# Data_Blue.net
KiCad netlist of a schematic drawn in Altium Designer
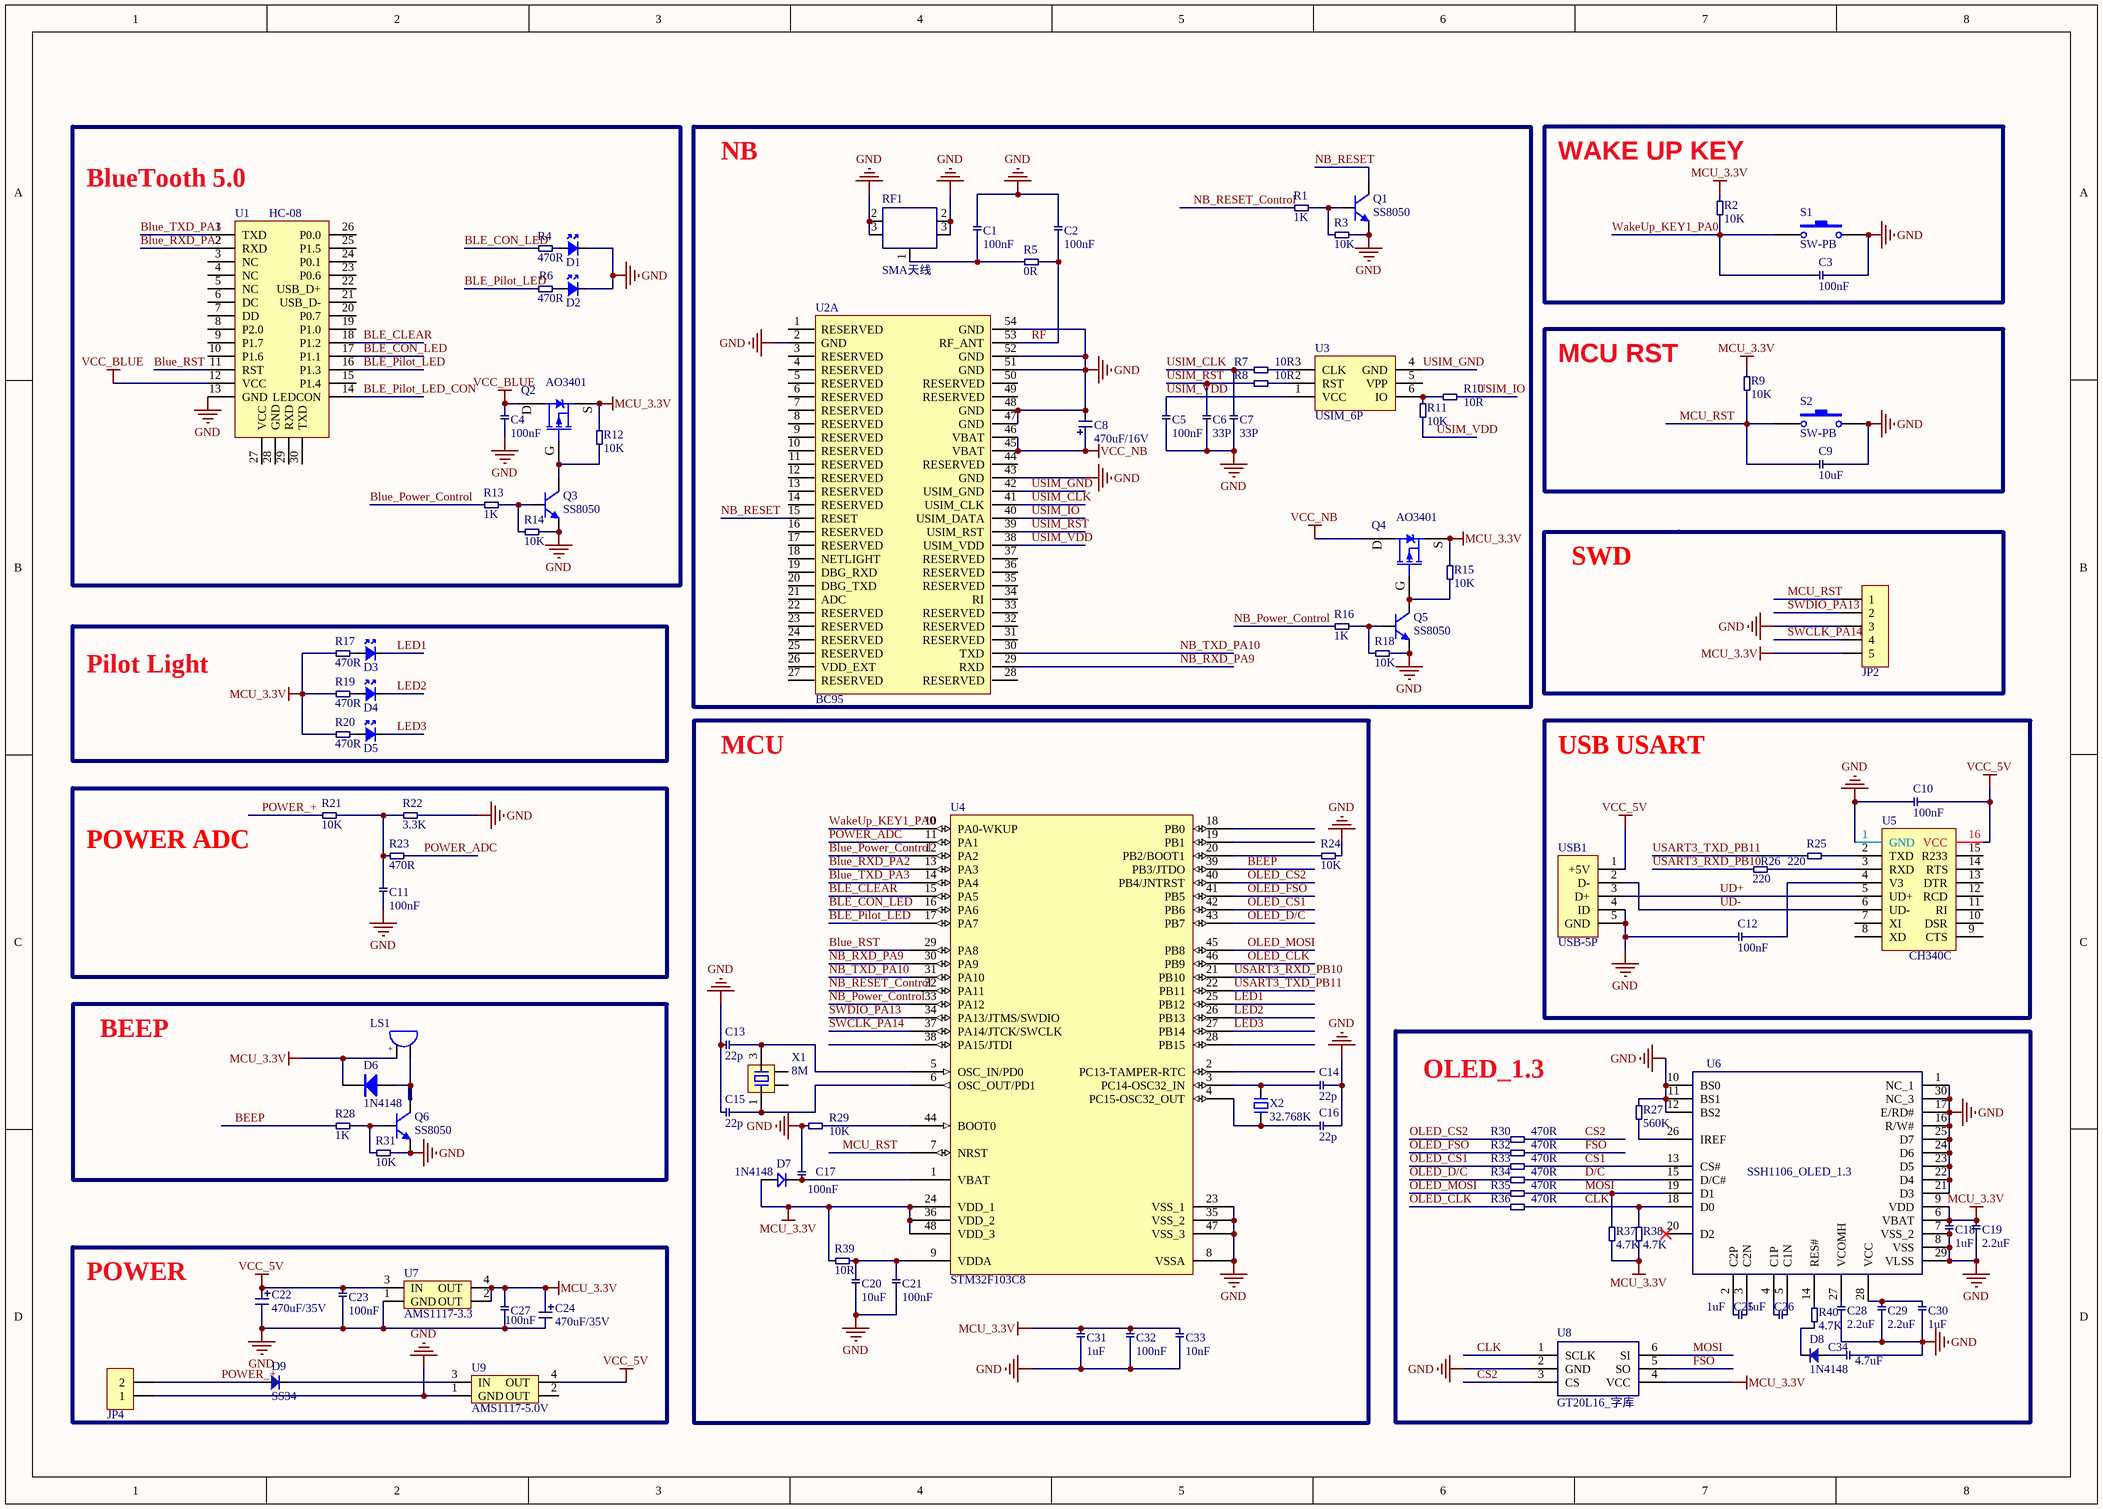
[diagram p0: Data_Blue.SchDoc]

(export (version "E")
  (design (tool "Eeschema 10.0.6"))
  (components
    (comp (ref "C1") (value "100nF") (footprint "0603CC") (libsource (lib "LFZ@WLP") (part "cap")))
    (comp (ref "C2") (value "100nF") (footprint "0603CC") (libsource (lib "LFZ@WLP") (part "cap")))
    (comp (ref "C3") (value "100nF") (footprint "0603CC") (libsource (lib "LFZ@WLP") (part "cap")))
    (comp (ref "C4") (value "100nF") (footprint "0603CC") (libsource (lib "LFZ@WLP") (part "cap")))
    (comp (ref "C5") (value "100nF") (footprint "0603CC") (libsource (lib "LFZ@WLP") (part "cap")))
    (comp (ref "C6") (value "33P") (footprint "0603CC") (libsource (lib "LFZ@WLP") (part "cap")))
    (comp (ref "C7") (value "33P") (footprint "0603CC") (libsource (lib "LFZ@WLP") (part "cap")))
    (comp (ref "C8") (value "470uF/16V") (footprint "C3216") (libsource (lib "LFZ@WLP") (part "Ecap")))
    (comp (ref "C9") (value "10uF") (footprint "0603CC") (libsource (lib "LFZ@WLP") (part "cap")))
    (comp (ref "C10") (value "100nF") (footprint "0603CC") (libsource (lib "LFZ@WLP") (part "cap")))
    (comp (ref "C11") (value "100nF") (footprint "0603CC") (libsource (lib "LFZ@WLP") (part "cap")))
    (comp (ref "C12") (value "100nF") (footprint "0603CC") (libsource (lib "LFZ@WLP") (part "cap")))
    (comp (ref "C13") (value "22p") (footprint "0603CC") (libsource (lib "LFZ@WLP") (part "cap")))
    (comp (ref "C14") (value "22p") (footprint "0603CC") (libsource (lib "LFZ@WLP") (part "cap")))
    (comp (ref "C15") (value "22p") (footprint "0603CC") (libsource (lib "LFZ@WLP") (part "cap")))
    (comp (ref "C16") (value "22p") (footprint "0603CC") (libsource (lib "LFZ@WLP") (part "cap")))
    (comp (ref "C17") (value "100nF") (footprint "0603CC") (libsource (lib "LFZ@WLP") (part "cap")))
    (comp (ref "C18") (value "1uF") (footprint "0603CC") (libsource (lib "LFZ@WLP") (part "cap")))
    (comp (ref "C19") (value "2.2uF") (footprint "0603CC") (libsource (lib "LFZ@WLP") (part "cap")))
    (comp (ref "C20") (value "10uF") (footprint "0603CC") (libsource (lib "LFZ@WLP") (part "cap")))
    (comp (ref "C21") (value "100nF") (footprint "0603CC") (libsource (lib "LFZ@WLP") (part "cap")))
    (comp (ref "C22") (value "470uF/35V") (footprint "CD A(3216)") (libsource (lib "LFZ@WLP") (part "Ecap")))
    (comp (ref "C23") (value "100nF") (footprint "0603CC") (libsource (lib "LFZ@WLP") (part "cap")))
    (comp (ref "C24") (value "470uF/35V") (footprint "C3216") (libsource (lib "LFZ@WLP") (part "Ecap")))
    (comp (ref "C25") (value "1uF") (footprint "0603CC") (libsource (lib "LFZ@WLP") (part "cap")))
    (comp (ref "C26") (value "1uF") (footprint "0603CC") (libsource (lib "LFZ@WLP") (part "cap")))
    (comp (ref "C27") (value "100nF") (footprint "0603CC") (libsource (lib "LFZ@WLP") (part "cap")))
    (comp (ref "C28") (value "2.2uF") (footprint "0603CC") (libsource (lib "LFZ@WLP") (part "cap")))
    (comp (ref "C29") (value "2.2uF") (footprint "0603CC") (libsource (lib "LFZ@WLP") (part "cap")))
    (comp (ref "C30") (value "1uF") (footprint "0603CC") (libsource (lib "LFZ@WLP") (part "cap")))
    (comp (ref "C31") (value "1uF") (footprint "0603CC") (libsource (lib "LFZ@WLP") (part "cap")))
    (comp (ref "C32") (value "100nF") (footprint "0603CC") (libsource (lib "LFZ@WLP") (part "cap")))
    (comp (ref "C33") (value "10nF") (footprint "0603CC") (libsource (lib "LFZ@WLP") (part "cap")))
    (comp (ref "C34") (value "4.7uF") (footprint "0603CC") (libsource (lib "LFZ@WLP") (part "cap")))
    (comp (ref "D1") (value "LED") (footprint "LED 0603G") (libsource (lib "LFZ@WLP") (part "LED")))
    (comp (ref "D2") (value "LED") (footprint "LED 0603R") (libsource (lib "LFZ@WLP") (part "LED")))
    (comp (ref "D3") (value "LED") (footprint "LED 3MM-G") (libsource (lib "LFZ@WLP") (part "LED")))
    (comp (ref "D4") (value "LED") (footprint "LED 3MM-G") (libsource (lib "LFZ@WLP") (part "LED")))
    (comp (ref "D5") (value "LED") (footprint "LED 3MM-G") (libsource (lib "LFZ@WLP") (part "LED")))
    (comp (ref "D6")
      (value "1N4148")
      (footprint "SOD-323")
      (description "高速开关二极管")
      (libsource (lib "8.1   - 二极管-整流桥") (part "1N4148"))
    )
    (comp (ref "D7")
      (value "1N4148")
      (footprint "SOD-323")
      (libsource (lib "WarShip V3 STM32103封装库") (part "D"))
    )
    (comp (ref "D8") (value "1N4148") (footprint "SOD-523") (libsource (lib "LFZ@WLP") (part "Diod")))
    (comp (ref "D9") (value "SS34") (footprint "SMA") (libsource (lib "Diod") (part "Diod")))
    (comp (ref "JP2")
      (value "HDR-1X5")
      (footprint "HDR2.54-LI-5P")
      (description "5P接插件")
      (libsource (lib "4.5   - 接插件-脚距2.54") (part "Header 5"))
    )
    (comp (ref "JP4")
      (value "HDR-1X2")
      (footprint "XH2.54-WI-2P")
      (description "2P接插件")
      (libsource (lib "4.5   - 接插件-脚距2.54") (part "Header 2"))
    )
    (comp (ref "LS1")
      (value "DC5V")
      (footprint "BEEP 5x9x5.5")
      (description "蜂鸣器")
      (libsource (lib "15.1 - 未分类器件") (part "BEEP"))
    )
    (comp (ref "Q1")
      (value "SS8050")
      (footprint "SOT23-3N")
      (description "高频放大-NPN型")
      (libsource (lib "6.2   - 三极管") (part "8050-SMD"))
    )
    (comp (ref "Q2")
      (value "AO3401")
      (footprint "SOT23-3N")
      (description "P沟道场效应管")
      (libsource (lib "6.1   - 场效应管-可控硅") (part "SI2301"))
    )
    (comp (ref "Q3")
      (value "SS8050")
      (footprint "SOT23-3N")
      (description "高频放大-NPN型")
      (libsource (lib "6.2   - 三极管") (part "8050-SMD"))
    )
    (comp (ref "Q4")
      (value "AO3401")
      (footprint "SOT23-3N")
      (description "P沟道场效应管")
      (libsource (lib "6.1   - 场效应管-可控硅") (part "SI2301"))
    )
    (comp (ref "Q5")
      (value "SS8050")
      (footprint "SOT23-3N")
      (description "高频放大-NPN型")
      (libsource (lib "6.2   - 三极管") (part "8050-SMD"))
    )
    (comp (ref "Q6")
      (value "SS8050")
      (footprint "SOT23-3N")
      (description "高频放大-NPN型")
      (libsource (lib "6.2   - 三极管") (part "8050-SMD"))
    )
    (comp (ref "R1") (value "1K") (footprint "0603RR") (libsource (lib "LFZ@WLP") (part "res")))
    (comp (ref "R2") (value "10K") (footprint "0603RR") (libsource (lib "LFZ@WLP") (part "res")))
    (comp (ref "R3") (value "10K") (footprint "0603RR") (libsource (lib "LFZ@WLP") (part "res")))
    (comp (ref "R4") (value "470R") (footprint "0603RR") (libsource (lib "LFZ@WLP") (part "res")))
    (comp (ref "R5") (value "0R") (footprint "0603RR") (libsource (lib "LFZ@WLP") (part "res")))
    (comp (ref "R6") (value "470R") (footprint "0603RR") (libsource (lib "LFZ@WLP") (part "res")))
    (comp (ref "R7") (value "10R") (footprint "0603RR") (libsource (lib "LFZ@WLP") (part "res")))
    (comp (ref "R8") (value "10R") (footprint "0603RR") (libsource (lib "LFZ@WLP") (part "res")))
    (comp (ref "R9") (value "10K") (footprint "0603RR") (libsource (lib "LFZ@WLP") (part "res")))
    (comp (ref "R10") (value "10R") (footprint "0603RR") (libsource (lib "LFZ@WLP") (part "res")))
    (comp (ref "R11") (value "10K") (footprint "0603RR") (libsource (lib "LFZ@WLP") (part "res")))
    (comp (ref "R12") (value "10K") (footprint "0603RR") (libsource (lib "LFZ@WLP") (part "res")))
    (comp (ref "R13") (value "1K") (footprint "0603RR") (libsource (lib "LFZ@WLP") (part "res")))
    (comp (ref "R14") (value "10K") (footprint "0603RR") (libsource (lib "LFZ@WLP") (part "res")))
    (comp (ref "R15") (value "10K") (footprint "0603RR") (libsource (lib "LFZ@WLP") (part "res")))
    (comp (ref "R16") (value "1K") (footprint "0603RR") (libsource (lib "LFZ@WLP") (part "res")))
    (comp (ref "R17") (value "470R") (footprint "0603RR") (libsource (lib "LFZ@WLP") (part "res")))
    (comp (ref "R18") (value "10K") (footprint "0603RR") (libsource (lib "LFZ@WLP") (part "res")))
    (comp (ref "R19") (value "470R") (footprint "0603RR") (libsource (lib "LFZ@WLP") (part "res")))
    (comp (ref "R20") (value "470R") (footprint "0603RR") (libsource (lib "LFZ@WLP") (part "res")))
    (comp (ref "R21") (value "10K") (footprint "0603RR") (libsource (lib "LFZ@WLP") (part "res")))
    (comp (ref "R22") (value "3.3K") (footprint "0603RR") (libsource (lib "LFZ@WLP") (part "res")))
    (comp (ref "R23") (value "470R") (footprint "0603RR") (libsource (lib "LFZ@WLP") (part "res")))
    (comp (ref "R24") (value "10K") (footprint "0603RR") (libsource (lib "LFZ@WLP") (part "res")))
    (comp (ref "R25") (value "220") (footprint "0603RR") (libsource (lib "LFZ@WLP") (part "res")))
    (comp (ref "R26") (value "220") (footprint "0603RR") (libsource (lib "LFZ@WLP") (part "res")))
    (comp (ref "R27") (value "560K") (footprint "0603RR") (libsource (lib "LFZ@WLP") (part "res")))
    (comp (ref "R28") (value "1K") (footprint "0603RR") (libsource (lib "LFZ@WLP") (part "res")))
    (comp (ref "R29") (value "10K") (footprint "0603RR") (libsource (lib "LFZ@WLP") (part "res")))
    (comp (ref "R30") (value "470R") (footprint "0603RR") (libsource (lib "LFZ@WLP") (part "res")))
    (comp (ref "R31") (value "10K") (footprint "0603RR") (libsource (lib "LFZ@WLP") (part "res")))
    (comp (ref "R32") (value "470R") (footprint "0603RR") (libsource (lib "LFZ@WLP") (part "res")))
    (comp (ref "R33") (value "470R") (footprint "0603RR") (libsource (lib "LFZ@WLP") (part "res")))
    (comp (ref "R34") (value "470R") (footprint "0603RR") (libsource (lib "LFZ@WLP") (part "res")))
    (comp (ref "R35") (value "470R") (footprint "0603RR") (libsource (lib "LFZ@WLP") (part "res")))
    (comp (ref "R36") (value "470R") (footprint "0603RR") (libsource (lib "LFZ@WLP") (part "res")))
    (comp (ref "R37") (value "4.7K") (footprint "0603RR") (libsource (lib "LFZ@WLP") (part "res")))
    (comp (ref "R38") (value "4.7K") (footprint "0603RR") (libsource (lib "LFZ@WLP") (part "res")))
    (comp (ref "R39") (value "10R") (footprint "0603RR") (libsource (lib "LFZ@WLP") (part "res")))
    (comp (ref "R40") (value "4.7K") (footprint "0603RR") (libsource (lib "LFZ@WLP") (part "res")))
    (comp (ref "RF1") (value "SMA天线") (footprint "SMA_FR") (libsource (lib "LFZ@WLP") (part "SMA天线")))
    (comp (ref "S1")
      (value "SW-PB")
      (footprint "TSW SMD-6*6*6")
      (description "Switch")
      (libsource (lib "开关及电源") (part "SW-PB"))
    )
    (comp (ref "S2")
      (value "SW-PB")
      (footprint "TSW SMD-4*4*1.5")
      (description "Switch")
      (libsource (lib "开关及电源") (part "SW-PB"))
    )
    (comp (ref "U1") (value "HC-08") (footprint "HC-08") (libsource (lib "LFZ@WLP") (part "HC-08")))
    (comp (ref "U2")
      (value "BC95")
      (footprint "BC95")
      (libsource (lib "Quectel_BC95_SCH_Part_Protel&AD_20170925") (part "BC95"))
    )
    (comp (ref "U3") (value "USIM_6P") (footprint "SIM 6P 自弹") (libsource (lib "XG-BM02") (part "USIM-6P")))
    (comp (ref "U4")
      (value "STM32F103C8")
      (footprint "LQFP48 7X7_M")
      (description "Flaah:64/RAM:20/IO:36")
      (libsource (lib "2.1   - STM32系列单片机") (part "STM32F103C8"))
    )
    (comp (ref "U5") (value "CH340C") (footprint "SOP16_L") (libsource (lib "LFZ@WLP") (part "CH340C")))
    (comp (ref "U6")
      (value "SSH1106_OLED_1.3")
      (footprint "OLED_1.3_FPC_30")
      (libsource (lib "LFZ@WLP") (part "SSH1106_OLED_1.3"))
    )
    (comp (ref "U7")
      (value "AMS1117-3.3")
      (footprint "SOT223_N")
      (libsource (lib "WarShip V3 STM32103封装库") (part "AMS1117"))
    )
    (comp (ref "U8")
      (value "GT20L16_字库")
      (footprint "SOT23-6")
      (libsource (lib "LFZ@WLP") (part "GT20L16_字库"))
    )
    (comp (ref "U9")
      (value "AMS1117-5.0V")
      (footprint "SOT223_N")
      (libsource (lib "WarShip V3 STM32103封装库") (part "AMS1117"))
    )
    (comp (ref "USB1")
      (value "USB-5P")
      (footprint "USB-MICRO_A")
      (description "微型USB母座")
      (libsource (lib "4.1   - 接口类") (part "USB-5P"))
    )
    (comp (ref "X1")
      (value "8M")
      (footprint "OSC 3225-4P")
      (description "4脚无源晶振")
      (libsource (lib "10.1 - 保险丝-晶振") (part "XTAL-4P"))
    )
    (comp (ref "X2")
      (value "32.768K")
      (footprint "OSC 3215-2P")
      (description "2脚无源脚晶振")
      (libsource (lib "10.1 - 保险丝-晶振") (part "XTAL-2P"))
    )
  )
  (nets
    (net (code "1") (name "/BEEP") (class "Default")
      (node (ref "R28") (pin "1") (pinfunction "1_1") (pintype "passive"))
      (node (ref "U4") (pin "39") (pinfunction "PB3/JTDO_39") (pintype "bidirectional"))
    )
    (net (code "2") (name "/BLE_CLEAR") (class "Default")
      (node (ref "U1") (pin "18") (pinfunction "P1.2_18") (pintype "passive"))
      (node (ref "U4") (pin "15") (pinfunction "PA5_15") (pintype "bidirectional"))
    )
    (net (code "3") (name "/BLE_CON_LED") (class "Default")
      (node (ref "R4") (pin "1") (pinfunction "1_1") (pintype "passive"))
      (node (ref "U1") (pin "17") (pinfunction "P1.1_17") (pintype "passive"))
      (node (ref "U4") (pin "16") (pinfunction "PA6_16") (pintype "bidirectional"))
    )
    (net (code "4") (name "/BLE_Pilot_LED") (class "Default")
      (node (ref "R6") (pin "1") (pinfunction "1_1") (pintype "passive"))
      (node (ref "U1") (pin "16") (pinfunction "P1.3_16") (pintype "passive"))
      (node (ref "U4") (pin "17") (pinfunction "PA7_17") (pintype "bidirectional"))
    )
    (net (code "5") (name "/BLE_Pilot_LED_CON") (class "Default")
      (node (ref "U1") (pin "14") (pinfunction "LEDCON_14") (pintype "passive"))
    )
    (net (code "6") (name "/Blue_Power_Control") (class "Default")
      (node (ref "R13") (pin "1") (pinfunction "1_1") (pintype "passive"))
      (node (ref "U4") (pin "12") (pinfunction "PA2_12") (pintype "bidirectional"))
    )
    (net (code "7") (name "/Blue_RST") (class "Default")
      (node (ref "U1") (pin "11") (pinfunction "RST_11") (pintype "passive"))
      (node (ref "U4") (pin "29") (pinfunction "PA8_29") (pintype "bidirectional"))
    )
    (net (code "8") (name "/Blue_RXD_PA2") (class "Default")
      (node (ref "U1") (pin "2") (pinfunction "RXD_2") (pintype "passive"))
      (node (ref "U4") (pin "13") (pinfunction "PA3_13") (pintype "bidirectional"))
    )
    (net (code "9") (name "/Blue_TXD_PA3") (class "Default")
      (node (ref "U1") (pin "1") (pinfunction "TXD_1") (pintype "passive"))
      (node (ref "U4") (pin "14") (pinfunction "PA4_14") (pintype "bidirectional"))
    )
    (net (code "10") (name "/CLK") (class "Default")
      (node (ref "R36") (pin "2") (pinfunction "2_2") (pintype "passive"))
      (node (ref "R38") (pin "2") (pinfunction "2_2") (pintype "passive"))
      (node (ref "U6") (pin "18") (pinfunction "D0_18") (pintype "passive"))
      (node (ref "U8") (pin "1") (pinfunction "SCLK_1") (pintype "passive"))
    )
    (net (code "11") (name "/CS1") (class "Default")
      (node (ref "R33") (pin "2") (pinfunction "2_2") (pintype "passive"))
      (node (ref "U6") (pin "13") (pinfunction "CS#_13") (pintype "passive"))
    )
    (net (code "12") (name "/CS2") (class "Default")
      (node (ref "R30") (pin "2") (pinfunction "2_2") (pintype "passive"))
      (node (ref "U8") (pin "3") (pinfunction "CS_3") (pintype "passive"))
    )
    (net (code "13") (name "/D{slash}C") (class "Default")
      (node (ref "R34") (pin "2") (pinfunction "2_2") (pintype "passive"))
      (node (ref "U6") (pin "15") (pinfunction "D/C#_15") (pintype "passive"))
    )
    (net (code "14") (name "/FSO") (class "Default")
      (node (ref "R32") (pin "2") (pinfunction "2_2") (pintype "passive"))
      (node (ref "U8") (pin "5") (pinfunction "SO_5") (pintype "passive"))
    )
    (net (code "15") (name "/LED1") (class "Default")
      (node (ref "D3") (pin "2") (pinfunction "CATHODE_2") (pintype "passive"))
      (node (ref "U4") (pin "25") (pinfunction "PB12_25") (pintype "bidirectional"))
    )
    (net (code "16") (name "/LED2") (class "Default")
      (node (ref "D4") (pin "2") (pinfunction "CATHODE_2") (pintype "passive"))
      (node (ref "U4") (pin "26") (pinfunction "PB13_26") (pintype "bidirectional"))
    )
    (net (code "17") (name "/LED3") (class "Default")
      (node (ref "D5") (pin "2") (pinfunction "CATHODE_2") (pintype "passive"))
      (node (ref "U4") (pin "27") (pinfunction "PB14_27") (pintype "bidirectional"))
    )
    (net (code "18") (name "/MCU_RST") (class "Default")
      (node (ref "C9") (pin "2") (pinfunction "2_2") (pintype "passive"))
      (node (ref "JP2") (pin "1") (pinfunction "1_1") (pintype "passive"))
      (node (ref "R9") (pin "1") (pinfunction "1_1") (pintype "passive"))
      (node (ref "S2") (pin "1") (pinfunction "1_1") (pintype "passive"))
      (node (ref "U4") (pin "7") (pinfunction "NRST_7") (pintype "bidirectional"))
    )
    (net (code "19") (name "/MOSI") (class "Default")
      (node (ref "R35") (pin "2") (pinfunction "2_2") (pintype "passive"))
      (node (ref "R37") (pin "2") (pinfunction "2_2") (pintype "passive"))
      (node (ref "U6") (pin "19") (pinfunction "D1_19") (pintype "passive"))
      (node (ref "U8") (pin "6") (pinfunction "SI_6") (pintype "passive"))
    )
    (net (code "20") (name "/NB_Power_Control") (class "Default")
      (node (ref "R16") (pin "1") (pinfunction "1_1") (pintype "passive"))
      (node (ref "U4") (pin "33") (pinfunction "PA12_33") (pintype "bidirectional"))
    )
    (net (code "21") (name "/NB_RESET") (class "Default")
      (node (ref "Q1") (pin "3") (pinfunction "C_3") (pintype "passive"))
      (node (ref "U2") (pin "15") (pinfunction "RESET_15") (pintype "passive"))
    )
    (net (code "22") (name "/NB_RESET_Control") (class "Default")
      (node (ref "R1") (pin "1") (pinfunction "1_1") (pintype "passive"))
      (node (ref "U4") (pin "32") (pinfunction "PA11_32") (pintype "bidirectional"))
    )
    (net (code "23") (name "/NB_RXD_PA9") (class "Default")
      (node (ref "U2") (pin "29") (pinfunction "RXD_29") (pintype "passive"))
      (node (ref "U4") (pin "30") (pinfunction "PA9_30") (pintype "bidirectional"))
    )
    (net (code "24") (name "/NB_TXD_PA10") (class "Default")
      (node (ref "U2") (pin "30") (pinfunction "TXD_30") (pintype "passive"))
      (node (ref "U4") (pin "31") (pinfunction "PA10_31") (pintype "bidirectional"))
    )
    (net (code "25") (name "/OLED_CLK") (class "Default")
      (node (ref "R36") (pin "1") (pinfunction "1_1") (pintype "passive"))
      (node (ref "U4") (pin "46") (pinfunction "PB9_46") (pintype "bidirectional"))
    )
    (net (code "26") (name "/OLED_CS1") (class "Default")
      (node (ref "R33") (pin "1") (pinfunction "1_1") (pintype "passive"))
      (node (ref "U4") (pin "42") (pinfunction "PB6_42") (pintype "bidirectional"))
    )
    (net (code "27") (name "/OLED_CS2") (class "Default")
      (node (ref "R30") (pin "1") (pinfunction "1_1") (pintype "passive"))
      (node (ref "U4") (pin "40") (pinfunction "PB4/JNTRST_40") (pintype "bidirectional"))
    )
    (net (code "28") (name "/OLED_D{slash}C") (class "Default")
      (node (ref "R34") (pin "1") (pinfunction "1_1") (pintype "passive"))
      (node (ref "U4") (pin "43") (pinfunction "PB7_43") (pintype "bidirectional"))
    )
    (net (code "29") (name "/OLED_FSO") (class "Default")
      (node (ref "R32") (pin "1") (pinfunction "1_1") (pintype "passive"))
      (node (ref "U4") (pin "41") (pinfunction "PB5_41") (pintype "bidirectional"))
    )
    (net (code "30") (name "/OLED_MOSI") (class "Default")
      (node (ref "R35") (pin "1") (pinfunction "1_1") (pintype "passive"))
      (node (ref "U4") (pin "45") (pinfunction "PB8_45") (pintype "bidirectional"))
    )
    (net (code "31") (name "/POWER_+") (class "Default")
      (node (ref "D9") (pin "1") (pinfunction "ANODE_1") (pintype "passive"))
      (node (ref "JP4") (pin "2") (pinfunction "2_2") (pintype "passive"))
      (node (ref "R21") (pin "1") (pinfunction "1_1") (pintype "passive"))
    )
    (net (code "32") (name "/POWER_ADC") (class "Default")
      (node (ref "R23") (pin "1") (pinfunction "1_1") (pintype "passive"))
      (node (ref "U4") (pin "11") (pinfunction "PA1_11") (pintype "bidirectional"))
    )
    (net (code "33") (name "/RF") (class "Default")
      (node (ref "C2") (pin "1") (pinfunction "1_1") (pintype "passive"))
      (node (ref "R5") (pin "1") (pinfunction "1_1") (pintype "passive"))
      (node (ref "U2") (pin "53") (pinfunction "RF_ANT_53") (pintype "passive"))
    )
    (net (code "34") (name "/SWCLK_PA14") (class "Default")
      (node (ref "JP2") (pin "4") (pinfunction "4_4") (pintype "passive"))
      (node (ref "U4") (pin "37") (pinfunction "PA14/JTCK/SWCLK_37") (pintype "bidirectional"))
    )
    (net (code "35") (name "/SWDIO_PA13") (class "Default")
      (node (ref "JP2") (pin "2") (pinfunction "2_2") (pintype "passive"))
      (node (ref "U4") (pin "34") (pinfunction "PA13/JTMS/SWDIO_34") (pintype "bidirectional"))
    )
    (net (code "36") (name "/UD+") (class "Default")
      (node (ref "U5") (pin "5") (pinfunction "UD+_5") (pintype "passive"))
      (node (ref "USB1") (pin "3") (pinfunction "D+_3") (pintype "passive"))
    )
    (net (code "37") (name "/UD-") (class "Default")
      (node (ref "U5") (pin "6") (pinfunction "UD-_6") (pintype "passive"))
      (node (ref "USB1") (pin "2") (pinfunction "D-_2") (pintype "passive"))
    )
    (net (code "38") (name "/USART3_RXD_PB10") (class "Default")
      (node (ref "R26") (pin "1") (pinfunction "1_1") (pintype "passive"))
      (node (ref "U4") (pin "21") (pinfunction "PB10_21") (pintype "bidirectional"))
    )
    (net (code "39") (name "/USART3_TXD_PB11") (class "Default")
      (node (ref "R25") (pin "1") (pinfunction "1_1") (pintype "passive"))
      (node (ref "U4") (pin "22") (pinfunction "PB11_22") (pintype "bidirectional"))
    )
    (net (code "40") (name "/USIM_CLK") (class "Default")
      (node (ref "C7") (pin "2") (pinfunction "2_2") (pintype "passive"))
      (node (ref "R7") (pin "1") (pinfunction "1_1") (pintype "passive"))
      (node (ref "U2") (pin "41") (pinfunction "USIM_CLK_41") (pintype "passive"))
    )
    (net (code "41") (name "/USIM_GND") (class "Default")
      (node (ref "U2") (pin "42") (pinfunction "USIM_GND_42") (pintype "passive"))
      (node (ref "U3") (pin "4") (pinfunction "GND_4") (pintype "passive"))
    )
    (net (code "42") (name "/USIM_IO") (class "Default")
      (node (ref "R10") (pin "1") (pinfunction "1_1") (pintype "passive"))
      (node (ref "U2") (pin "40") (pinfunction "USIM_DATA_40") (pintype "passive"))
    )
    (net (code "43") (name "/USIM_RST") (class "Default")
      (node (ref "C6") (pin "2") (pinfunction "2_2") (pintype "passive"))
      (node (ref "R8") (pin "1") (pinfunction "1_1") (pintype "passive"))
      (node (ref "U2") (pin "39") (pinfunction "USIM_RST_39") (pintype "passive"))
    )
    (net (code "44") (name "/USIM_VDD") (class "Default")
      (node (ref "C5") (pin "2") (pinfunction "2_2") (pintype "passive"))
      (node (ref "R11") (pin "1") (pinfunction "1_1") (pintype "passive"))
      (node (ref "U2") (pin "38") (pinfunction "USIM_VDD_38") (pintype "passive"))
      (node (ref "U3") (pin "1") (pinfunction "VCC_1") (pintype "passive"))
    )
    (net (code "45") (name "/WakeUp_KEY1_PA0") (class "Default")
      (node (ref "C3") (pin "1") (pinfunction "1_1") (pintype "passive"))
      (node (ref "R2") (pin "1") (pinfunction "1_1") (pintype "passive"))
      (node (ref "S1") (pin "1") (pinfunction "1_1") (pintype "passive"))
      (node (ref "U4") (pin "10") (pinfunction "PA0-WKUP_10") (pintype "bidirectional"))
    )
    (net (code "46") (name "GND") (class "Default")
      (node (ref "C1") (pin "2") (pinfunction "2_2") (pintype "passive"))
      (node (ref "C10") (pin "2") (pinfunction "2_2") (pintype "passive"))
      (node (ref "C11") (pin "1") (pinfunction "1_1") (pintype "passive"))
      (node (ref "C12") (pin "2") (pinfunction "2_2") (pintype "passive"))
      (node (ref "C13") (pin "1") (pinfunction "1_1") (pintype "passive"))
      (node (ref "C14") (pin "2") (pinfunction "2_2") (pintype "passive"))
      (node (ref "C15") (pin "1") (pinfunction "1_1") (pintype "passive"))
      (node (ref "C16") (pin "2") (pinfunction "2_2") (pintype "passive"))
      (node (ref "C17") (pin "2") (pinfunction "2_2") (pintype "passive"))
      (node (ref "C18") (pin "1") (pinfunction "1_1") (pintype "passive"))
      (node (ref "C19") (pin "1") (pinfunction "1_1") (pintype "passive"))
      (node (ref "C2") (pin "2") (pinfunction "2_2") (pintype "passive"))
      (node (ref "C20") (pin "1") (pinfunction "1_1") (pintype "passive"))
      (node (ref "C21") (pin "1") (pinfunction "1_1") (pintype "passive"))
      (node (ref "C22") (pin "2") (pinfunction "2_2") (pintype "passive"))
      (node (ref "C23") (pin "1") (pinfunction "1_1") (pintype "passive"))
      (node (ref "C24") (pin "2") (pinfunction "2_2") (pintype "passive"))
      (node (ref "C27") (pin "1") (pinfunction "1_1") (pintype "passive"))
      (node (ref "C28") (pin "1") (pinfunction "1_1") (pintype "passive"))
      (node (ref "C29") (pin "1") (pinfunction "1_1") (pintype "passive"))
      (node (ref "C3") (pin "2") (pinfunction "2_2") (pintype "passive"))
      (node (ref "C30") (pin "1") (pinfunction "1_1") (pintype "passive"))
      (node (ref "C31") (pin "1") (pinfunction "1_1") (pintype "passive"))
      (node (ref "C32") (pin "1") (pinfunction "1_1") (pintype "passive"))
      (node (ref "C33") (pin "1") (pinfunction "1_1") (pintype "passive"))
      (node (ref "C34") (pin "1") (pinfunction "1_1") (pintype "passive"))
      (node (ref "C4") (pin "1") (pinfunction "1_1") (pintype "passive"))
      (node (ref "C5") (pin "1") (pinfunction "1_1") (pintype "passive"))
      (node (ref "C6") (pin "1") (pinfunction "1_1") (pintype "passive"))
      (node (ref "C7") (pin "1") (pinfunction "1_1") (pintype "passive"))
      (node (ref "C8") (pin "2") (pinfunction "2_2") (pintype "passive"))
      (node (ref "C9") (pin "1") (pinfunction "1_1") (pintype "passive"))
      (node (ref "D1") (pin "2") (pinfunction "CATHODE_2") (pintype "passive"))
      (node (ref "D2") (pin "2") (pinfunction "CATHODE_2") (pintype "passive"))
      (node (ref "JP2") (pin "3") (pinfunction "3_3") (pintype "passive"))
      (node (ref "JP4") (pin "1") (pinfunction "1_1") (pintype "passive"))
      (node (ref "Q1") (pin "2") (pinfunction "E_2") (pintype "passive"))
      (node (ref "Q3") (pin "2") (pinfunction "E_2") (pintype "passive"))
      (node (ref "Q5") (pin "2") (pinfunction "E_2") (pintype "passive"))
      (node (ref "Q6") (pin "2") (pinfunction "E_2") (pintype "passive"))
      (node (ref "R14") (pin "2") (pinfunction "2_2") (pintype "passive"))
      (node (ref "R18") (pin "2") (pinfunction "2_2") (pintype "passive"))
      (node (ref "R22") (pin "2") (pinfunction "2_2") (pintype "passive"))
      (node (ref "R24") (pin "2") (pinfunction "2_2") (pintype "passive"))
      (node (ref "R27") (pin "2") (pinfunction "2_2") (pintype "passive"))
      (node (ref "R29") (pin "1") (pinfunction "1_1") (pintype "passive"))
      (node (ref "R3") (pin "2") (pinfunction "2_2") (pintype "passive"))
      (node (ref "R31") (pin "2") (pinfunction "2_2") (pintype "passive"))
      (node (ref "RF1") (pin "2") (pinfunction "5_2") (pintype "passive"))
      (node (ref "RF1") (pin "3") (pinfunction "3_3") (pintype "passive"))
      (node (ref "S1") (pin "2") (pinfunction "2_2") (pintype "passive"))
      (node (ref "S2") (pin "2") (pinfunction "2_2") (pintype "passive"))
      (node (ref "U1") (pin "13") (pinfunction "GND_13") (pintype "passive"))
      (node (ref "U2") (pin "2") (pinfunction "GND_2") (pintype "passive"))
      (node (ref "U2") (pin "43") (pinfunction "GND_43") (pintype "passive"))
      (node (ref "U2") (pin "47") (pinfunction "GND_47") (pintype "passive"))
      (node (ref "U2") (pin "48") (pinfunction "GND_48") (pintype "passive"))
      (node (ref "U2") (pin "51") (pinfunction "GND_51") (pintype "passive"))
      (node (ref "U2") (pin "52") (pinfunction "GND_52") (pintype "passive"))
      (node (ref "U2") (pin "54") (pinfunction "GND_54") (pintype "passive"))
      (node (ref "U4") (pin "23") (pinfunction "VSS_1_23") (pintype "power_in"))
      (node (ref "U4") (pin "35") (pinfunction "VSS_2_35") (pintype "power_in"))
      (node (ref "U4") (pin "47") (pinfunction "VSS_3_47") (pintype "power_in"))
      (node (ref "U4") (pin "8") (pinfunction "VSSA_8") (pintype "power_in"))
      (node (ref "U5") (pin "1") (pinfunction "GND_1") (pintype "passive"))
      (node (ref "U6") (pin "1") (pinfunction "NC_1_1") (pintype "passive"))
      (node (ref "U6") (pin "10") (pinfunction "BS0_10") (pintype "passive"))
      (node (ref "U6") (pin "11") (pinfunction "BS1_11") (pintype "passive"))
      (node (ref "U6") (pin "12") (pinfunction "BS2_12") (pintype "passive"))
      (node (ref "U6") (pin "16") (pinfunction "R/W#_16") (pintype "passive"))
      (node (ref "U6") (pin "17") (pinfunction "E/RD#_17") (pintype "passive"))
      (node (ref "U6") (pin "21") (pinfunction "D3_21") (pintype "passive"))
      (node (ref "U6") (pin "22") (pinfunction "D4_22") (pintype "passive"))
      (node (ref "U6") (pin "23") (pinfunction "D5_23") (pintype "passive"))
      (node (ref "U6") (pin "24") (pinfunction "D6_24") (pintype "passive"))
      (node (ref "U6") (pin "25") (pinfunction "D7_25") (pintype "passive"))
      (node (ref "U6") (pin "29") (pinfunction "VLSS_29") (pintype "passive"))
      (node (ref "U6") (pin "30") (pinfunction "NC_3_30") (pintype "passive"))
      (node (ref "U6") (pin "7") (pinfunction "VSS_2_7") (pintype "passive"))
      (node (ref "U6") (pin "8") (pinfunction "VSS_8") (pintype "passive"))
      (node (ref "U7") (pin "1") (pinfunction "GND_1") (pintype "passive"))
      (node (ref "U8") (pin "2") (pinfunction "GND_2") (pintype "passive"))
      (node (ref "U9") (pin "1") (pinfunction "GND_1") (pintype "passive"))
      (node (ref "USB1") (pin "4") (pinfunction "ID_4") (pintype "passive"))
      (node (ref "USB1") (pin "5") (pinfunction "GND_5") (pintype "passive"))
    )
    (net (code "47") (name "MCU_3.3V") (class "Default")
      (node (ref "C18") (pin "2") (pinfunction "2_2") (pintype "passive"))
      (node (ref "C19") (pin "2") (pinfunction "2_2") (pintype "passive"))
      (node (ref "C24") (pin "1") (pinfunction "1_1") (pintype "passive"))
      (node (ref "C27") (pin "2") (pinfunction "2_2") (pintype "passive"))
      (node (ref "C31") (pin "2") (pinfunction "2_2") (pintype "passive"))
      (node (ref "C32") (pin "2") (pinfunction "2_2") (pintype "passive"))
      (node (ref "C33") (pin "2") (pinfunction "2_2") (pintype "passive"))
      (node (ref "D6") (pin "2") (pinfunction "K_2") (pintype "passive"))
      (node (ref "D7") (pin "1") (pintype "passive"))
      (node (ref "JP2") (pin "5") (pinfunction "5_5") (pintype "passive"))
      (node (ref "LS1") (pin "1") (pinfunction "1_1") (pintype "passive"))
      (node (ref "Q2") (pin "2") (pinfunction "S_2") (pintype "passive"))
      (node (ref "Q4") (pin "2") (pinfunction "S_2") (pintype "passive"))
      (node (ref "R12") (pin "2") (pinfunction "2_2") (pintype "passive"))
      (node (ref "R15") (pin "2") (pinfunction "2_2") (pintype "passive"))
      (node (ref "R17") (pin "1") (pinfunction "1_1") (pintype "passive"))
      (node (ref "R19") (pin "1") (pinfunction "1_1") (pintype "passive"))
      (node (ref "R2") (pin "2") (pinfunction "2_2") (pintype "passive"))
      (node (ref "R20") (pin "1") (pinfunction "1_1") (pintype "passive"))
      (node (ref "R37") (pin "1") (pinfunction "1_1") (pintype "passive"))
      (node (ref "R38") (pin "1") (pinfunction "1_1") (pintype "passive"))
      (node (ref "R39") (pin "1") (pinfunction "1_1") (pintype "passive"))
      (node (ref "R9") (pin "2") (pinfunction "2_2") (pintype "passive"))
      (node (ref "U4") (pin "24") (pinfunction "VDD_1_24") (pintype "power_in"))
      (node (ref "U4") (pin "36") (pinfunction "VDD_2_36") (pintype "power_in"))
      (node (ref "U4") (pin "48") (pinfunction "VDD_3_48") (pintype "power_in"))
      (node (ref "U6") (pin "6") (pinfunction "VBAT_6") (pintype "passive"))
      (node (ref "U6") (pin "9") (pinfunction "VDD_9") (pintype "passive"))
      (node (ref "U7") (pin "2") (pinfunction "OUT_2") (pintype "passive"))
      (node (ref "U7") (pin "4") (pinfunction "OUT_4") (pintype "passive"))
      (node (ref "U8") (pin "4") (pinfunction "VCC_4") (pintype "passive"))
    )
    (net (code "48") (name "Net-(C1-Pad1)") (class "Default")
      (node (ref "C1") (pin "1") (pinfunction "1_1") (pintype "passive"))
      (node (ref "R5") (pin "2") (pinfunction "2_2") (pintype "passive"))
      (node (ref "RF1") (pin "1") (pinfunction "1_1") (pintype "passive"))
    )
    (net (code "49") (name "Net-(C11-Pad2)") (class "Default")
      (node (ref "C11") (pin "2") (pinfunction "2_2") (pintype "passive"))
      (node (ref "R21") (pin "2") (pinfunction "2_2") (pintype "passive"))
      (node (ref "R22") (pin "1") (pinfunction "1_1") (pintype "passive"))
      (node (ref "R23") (pin "2") (pinfunction "2_2") (pintype "passive"))
    )
    (net (code "50") (name "Net-(D1-ANODE)") (class "Default")
      (node (ref "D1") (pin "1") (pinfunction "ANODE_1") (pintype "passive"))
      (node (ref "R4") (pin "2") (pinfunction "2_2") (pintype "passive"))
    )
    (net (code "51") (name "Net-(D2-ANODE)") (class "Default")
      (node (ref "D2") (pin "1") (pinfunction "ANODE_1") (pintype "passive"))
      (node (ref "R6") (pin "2") (pinfunction "2_2") (pintype "passive"))
    )
    (net (code "52") (name "Net-(D3-ANODE)") (class "Default")
      (node (ref "D3") (pin "1") (pinfunction "ANODE_1") (pintype "passive"))
      (node (ref "R17") (pin "2") (pinfunction "2_2") (pintype "passive"))
    )
    (net (code "53") (name "Net-(D4-ANODE)") (class "Default")
      (node (ref "D4") (pin "1") (pinfunction "ANODE_1") (pintype "passive"))
      (node (ref "R19") (pin "2") (pinfunction "2_2") (pintype "passive"))
    )
    (net (code "54") (name "Net-(D5-ANODE)") (class "Default")
      (node (ref "D5") (pin "1") (pinfunction "ANODE_1") (pintype "passive"))
      (node (ref "R20") (pin "2") (pinfunction "2_2") (pintype "passive"))
    )
    (net (code "55") (name "Net-(D6-A)") (class "Default")
      (node (ref "D6") (pin "1") (pinfunction "A_1") (pintype "passive"))
      (node (ref "LS1") (pin "2") (pinfunction "2_2") (pintype "passive"))
      (node (ref "Q6") (pin "3") (pinfunction "C_3") (pintype "passive"))
    )
    (net (code "56") (name "Net-(D8-ANODE)") (class "Default")
      (node (ref "C34") (pin "2") (pinfunction "2_2") (pintype "passive"))
      (node (ref "D8") (pin "1") (pinfunction "ANODE_1") (pintype "passive"))
    )
    (net (code "57") (name "Net-(D8-CATHODE)") (class "Default")
      (node (ref "D8") (pin "2") (pinfunction "CATHODE_2") (pintype "passive"))
      (node (ref "R40") (pin "2") (pinfunction "2_2") (pintype "passive"))
    )
    (net (code "58") (name "Net-(D9-CATHODE)") (class "Default")
      (node (ref "D9") (pin "2") (pinfunction "CATHODE_2") (pintype "passive"))
      (node (ref "U9") (pin "3") (pinfunction "IN_3") (pintype "passive"))
    )
    (net (code "59") (name "Net-(Q1-B)") (class "Default")
      (node (ref "Q1") (pin "1") (pinfunction "B_1") (pintype "passive"))
      (node (ref "R1") (pin "2") (pinfunction "2_2") (pintype "passive"))
      (node (ref "R3") (pin "1") (pinfunction "1_1") (pintype "passive"))
    )
    (net (code "60") (name "Net-(Q2-G)") (class "Default")
      (node (ref "Q2") (pin "1") (pinfunction "G_1") (pintype "passive"))
      (node (ref "Q3") (pin "3") (pinfunction "C_3") (pintype "passive"))
      (node (ref "R12") (pin "1") (pinfunction "1_1") (pintype "passive"))
    )
    (net (code "61") (name "Net-(Q3-B)") (class "Default")
      (node (ref "Q3") (pin "1") (pinfunction "B_1") (pintype "passive"))
      (node (ref "R13") (pin "2") (pinfunction "2_2") (pintype "passive"))
      (node (ref "R14") (pin "1") (pinfunction "1_1") (pintype "passive"))
    )
    (net (code "62") (name "Net-(Q4-G)") (class "Default")
      (node (ref "Q4") (pin "1") (pinfunction "G_1") (pintype "passive"))
      (node (ref "Q5") (pin "3") (pinfunction "C_3") (pintype "passive"))
      (node (ref "R15") (pin "1") (pinfunction "1_1") (pintype "passive"))
    )
    (net (code "63") (name "Net-(Q5-B)") (class "Default")
      (node (ref "Q5") (pin "1") (pinfunction "B_1") (pintype "passive"))
      (node (ref "R16") (pin "2") (pinfunction "2_2") (pintype "passive"))
      (node (ref "R18") (pin "1") (pinfunction "1_1") (pintype "passive"))
    )
    (net (code "64") (name "Net-(Q6-B)") (class "Default")
      (node (ref "Q6") (pin "1") (pinfunction "B_1") (pintype "passive"))
      (node (ref "R28") (pin "2") (pinfunction "2_2") (pintype "passive"))
      (node (ref "R31") (pin "1") (pinfunction "1_1") (pintype "passive"))
    )
    (net (code "65") (name "Net-(U3-CLK)") (class "Default")
      (node (ref "R7") (pin "2") (pinfunction "2_2") (pintype "passive"))
      (node (ref "U3") (pin "3") (pinfunction "CLK_3") (pintype "passive"))
    )
    (net (code "66") (name "Net-(U3-IO)") (class "Default")
      (node (ref "R10") (pin "2") (pinfunction "2_2") (pintype "passive"))
      (node (ref "R11") (pin "2") (pinfunction "2_2") (pintype "passive"))
      (node (ref "U3") (pin "6") (pinfunction "IO_6") (pintype "passive"))
    )
    (net (code "67") (name "Net-(U3-RST)") (class "Default")
      (node (ref "R8") (pin "2") (pinfunction "2_2") (pintype "passive"))
      (node (ref "U3") (pin "2") (pinfunction "RST_2") (pintype "passive"))
    )
    (net (code "68") (name "Net-(U4-BOOT0)") (class "Default")
      (node (ref "R29") (pin "2") (pinfunction "2_2") (pintype "passive"))
      (node (ref "U4") (pin "44") (pinfunction "BOOT0_44") (pintype "input"))
    )
    (net (code "69") (name "Net-(U4-OSC_IN{slash}PD0)") (class "Default")
      (node (ref "C13") (pin "2") (pinfunction "2_2") (pintype "passive"))
      (node (ref "U4") (pin "5") (pinfunction "OSC_IN/PD0_5") (pintype "input"))
      (node (ref "X1") (pin "3") (pinfunction "3_3") (pintype "passive"))
    )
    (net (code "70") (name "Net-(U4-OSC_OUT{slash}PD1)") (class "Default")
      (node (ref "C15") (pin "2") (pinfunction "2_2") (pintype "passive"))
      (node (ref "U4") (pin "6") (pinfunction "OSC_OUT/PD1_6") (pintype "output"))
      (node (ref "X1") (pin "1") (pinfunction "1_1") (pintype "passive"))
    )
    (net (code "71") (name "Net-(U4-PB2{slash}BOOT1)") (class "Default")
      (node (ref "R24") (pin "1") (pinfunction "1_1") (pintype "passive"))
      (node (ref "U4") (pin "20") (pinfunction "PB2/BOOT1_20") (pintype "bidirectional"))
    )
    (net (code "72") (name "Net-(U4-PC14-OSC32_IN)") (class "Default")
      (node (ref "C14") (pin "1") (pinfunction "1_1") (pintype "passive"))
      (node (ref "U4") (pin "3") (pinfunction "PC14-OSC32_IN_3") (pintype "bidirectional"))
      (node (ref "X2") (pin "2") (pinfunction "2_2") (pintype "passive"))
    )
    (net (code "73") (name "Net-(U4-PC15-OSC32_OUT)") (class "Default")
      (node (ref "C16") (pin "1") (pinfunction "1_1") (pintype "passive"))
      (node (ref "U4") (pin "4") (pinfunction "PC15-OSC32_OUT_4") (pintype "bidirectional"))
      (node (ref "X2") (pin "1") (pinfunction "1_1") (pintype "passive"))
    )
    (net (code "74") (name "Net-(U4-VBAT)") (class "Default")
      (node (ref "C17") (pin "1") (pinfunction "1_1") (pintype "passive"))
      (node (ref "D7") (pin "2") (pintype "passive"))
      (node (ref "U4") (pin "1") (pinfunction "VBAT_1") (pintype "power_in"))
    )
    (net (code "75") (name "Net-(U4-VDDA)") (class "Default")
      (node (ref "C20") (pin "2") (pinfunction "2_2") (pintype "passive"))
      (node (ref "C21") (pin "2") (pinfunction "2_2") (pintype "passive"))
      (node (ref "R39") (pin "2") (pinfunction "2_2") (pintype "passive"))
      (node (ref "U4") (pin "9") (pinfunction "VDDA_9") (pintype "power_in"))
    )
    (net (code "76") (name "Net-(U5-RXD)") (class "Default")
      (node (ref "R26") (pin "2") (pinfunction "2_2") (pintype "passive"))
      (node (ref "U5") (pin "3") (pinfunction "RXD_3") (pintype "passive"))
    )
    (net (code "77") (name "Net-(U5-TXD)") (class "Default")
      (node (ref "R25") (pin "2") (pinfunction "2_2") (pintype "passive"))
      (node (ref "U5") (pin "2") (pinfunction "TXD_2") (pintype "passive"))
    )
    (net (code "78") (name "Net-(U5-V3)") (class "Default")
      (node (ref "C12") (pin "1") (pinfunction "1_1") (pintype "passive"))
      (node (ref "U5") (pin "4") (pinfunction "V3_4") (pintype "passive"))
    )
    (net (code "79") (name "Net-(U6-C1N)") (class "Default")
      (node (ref "C26") (pin "2") (pinfunction "2_2") (pintype "passive"))
      (node (ref "U6") (pin "5") (pinfunction "C1N_5") (pintype "passive"))
    )
    (net (code "80") (name "Net-(U6-C1P)") (class "Default")
      (node (ref "C26") (pin "1") (pinfunction "1_1") (pintype "passive"))
      (node (ref "U6") (pin "4") (pinfunction "C1P_4") (pintype "passive"))
    )
    (net (code "81") (name "Net-(U6-C2N)") (class "Default")
      (node (ref "C25") (pin "2") (pinfunction "2_2") (pintype "passive"))
      (node (ref "U6") (pin "3") (pinfunction "C2N_3") (pintype "passive"))
    )
    (net (code "82") (name "Net-(U6-C2P)") (class "Default")
      (node (ref "C25") (pin "1") (pinfunction "1_1") (pintype "passive"))
      (node (ref "U6") (pin "2") (pinfunction "C2P_2") (pintype "passive"))
    )
    (net (code "83") (name "Net-(U6-IREF)") (class "Default")
      (node (ref "R27") (pin "1") (pinfunction "1_1") (pintype "passive"))
      (node (ref "U6") (pin "26") (pinfunction "IREF_26") (pintype "passive"))
    )
    (net (code "84") (name "Net-(U6-RES#)") (class "Default")
      (node (ref "R40") (pin "1") (pinfunction "1_1") (pintype "passive"))
      (node (ref "U6") (pin "14") (pinfunction "RES#_14") (pintype "passive"))
    )
    (net (code "85") (name "Net-(U6-VCC)") (class "Default")
      (node (ref "C29") (pin "2") (pinfunction "2_2") (pintype "passive"))
      (node (ref "C30") (pin "2") (pinfunction "2_2") (pintype "passive"))
      (node (ref "U6") (pin "28") (pinfunction "VCC_28") (pintype "passive"))
    )
    (net (code "86") (name "Net-(U6-VCOMH)") (class "Default")
      (node (ref "C28") (pin "2") (pinfunction "2_2") (pintype "passive"))
      (node (ref "U6") (pin "27") (pinfunction "VCOMH_27") (pintype "passive"))
    )
    (net (code "87") (name "VCC_5V") (class "Default")
      (node (ref "C10") (pin "1") (pinfunction "1_1") (pintype "passive"))
      (node (ref "C22") (pin "1") (pinfunction "1_1") (pintype "passive"))
      (node (ref "C23") (pin "2") (pinfunction "2_2") (pintype "passive"))
      (node (ref "U5") (pin "16") (pinfunction "VCC_16") (pintype "passive"))
      (node (ref "U7") (pin "3") (pinfunction "IN_3") (pintype "passive"))
      (node (ref "U9") (pin "4") (pinfunction "OUT_4") (pintype "passive"))
      (node (ref "USB1") (pin "1") (pinfunction "+5V_1") (pintype "passive"))
    )
    (net (code "88") (name "VCC_BLUE") (class "Default")
      (node (ref "C4") (pin "2") (pinfunction "2_2") (pintype "passive"))
      (node (ref "Q2") (pin "3") (pinfunction "D_3") (pintype "passive"))
      (node (ref "U1") (pin "12") (pinfunction "VCC_12") (pintype "passive"))
    )
    (net (code "89") (name "VCC_NB") (class "Default")
      (node (ref "C8") (pin "1") (pinfunction "1_1") (pintype "passive"))
      (node (ref "Q4") (pin "3") (pinfunction "D_3") (pintype "passive"))
      (node (ref "U2") (pin "45") (pinfunction "VBAT_45") (pintype "passive"))
      (node (ref "U2") (pin "46") (pinfunction "VBAT_46") (pintype "passive"))
    )
    (net (code "90") (name "unconnected-(U1-DC-Pad6)") (class "Default")
      (node (ref "U1") (pin "6") (pinfunction "DC_6") (pintype "passive"))
    )
    (net (code "91") (name "unconnected-(U1-DD-Pad7)") (class "Default")
      (node (ref "U1") (pin "7") (pinfunction "DD_7") (pintype "passive"))
    )
    (net (code "92") (name "unconnected-(U1-GND-Pad28)") (class "Default")
      (node (ref "U1") (pin "28") (pinfunction "GND_28") (pintype "passive"))
    )
    (net (code "93") (name "unconnected-(U1-NC-Pad3)") (class "Default")
      (node (ref "U1") (pin "3") (pinfunction "NC_3") (pintype "passive"))
    )
    (net (code "94") (name "unconnected-(U1-NC-Pad4)") (class "Default")
      (node (ref "U1") (pin "4") (pinfunction "NC_4") (pintype "passive"))
    )
    (net (code "95") (name "unconnected-(U1-NC-Pad5)") (class "Default")
      (node (ref "U1") (pin "5") (pinfunction "NC_5") (pintype "passive"))
    )
    (net (code "96") (name "unconnected-(U1-P0.0-Pad26)") (class "Default")
      (node (ref "U1") (pin "26") (pinfunction "P0.0_26") (pintype "passive"))
    )
    (net (code "97") (name "unconnected-(U1-P0.1-Pad24)") (class "Default")
      (node (ref "U1") (pin "24") (pinfunction "P0.1_24") (pintype "passive"))
    )
    (net (code "98") (name "unconnected-(U1-P0.6-Pad23)") (class "Default")
      (node (ref "U1") (pin "23") (pinfunction "P0.6_23") (pintype "passive"))
    )
    (net (code "99") (name "unconnected-(U1-P0.7-Pad20)") (class "Default")
      (node (ref "U1") (pin "20") (pinfunction "P0.7_20") (pintype "passive"))
    )
    (net (code "100") (name "unconnected-(U1-P1.0-Pad19)") (class "Default")
      (node (ref "U1") (pin "19") (pinfunction "P1.0_19") (pintype "passive"))
    )
    (net (code "101") (name "unconnected-(U1-P1.4-Pad15)") (class "Default")
      (node (ref "U1") (pin "15") (pinfunction "P1.4_15") (pintype "passive"))
    )
    (net (code "102") (name "unconnected-(U1-P1.5-Pad25)") (class "Default")
      (node (ref "U1") (pin "25") (pinfunction "P1.5_25") (pintype "passive"))
    )
    (net (code "103") (name "unconnected-(U1-P1.6-Pad10)") (class "Default")
      (node (ref "U1") (pin "10") (pinfunction "P1.6_10") (pintype "passive"))
    )
    (net (code "104") (name "unconnected-(U1-P1.7-Pad9)") (class "Default")
      (node (ref "U1") (pin "9") (pinfunction "P1.7_9") (pintype "passive"))
    )
    (net (code "105") (name "unconnected-(U1-P2.0-Pad8)") (class "Default")
      (node (ref "U1") (pin "8") (pinfunction "P2.0_8") (pintype "passive"))
    )
    (net (code "106") (name "unconnected-(U1-RXD-Pad29)") (class "Default")
      (node (ref "U1") (pin "29") (pinfunction "RXD_29") (pintype "passive"))
    )
    (net (code "107") (name "unconnected-(U1-TXD-Pad30)") (class "Default")
      (node (ref "U1") (pin "30") (pinfunction "TXD_30") (pintype "passive"))
    )
    (net (code "108") (name "unconnected-(U1-USB_D+-Pad22)") (class "Default")
      (node (ref "U1") (pin "22") (pinfunction "USB_D+_22") (pintype "passive"))
    )
    (net (code "109") (name "unconnected-(U1-USB_D--Pad21)") (class "Default")
      (node (ref "U1") (pin "21") (pinfunction "USB_D-_21") (pintype "passive"))
    )
    (net (code "110") (name "unconnected-(U1-VCC-Pad27)") (class "Default")
      (node (ref "U1") (pin "27") (pinfunction "VCC_27") (pintype "passive"))
    )
    (net (code "111") (name "unconnected-(U2A-ADC-Pad21)") (class "Default")
      (node (ref "U2") (pin "21") (pinfunction "ADC_21") (pintype "passive"))
    )
    (net (code "112") (name "unconnected-(U2A-DBG_RXD-Pad19)") (class "Default")
      (node (ref "U2") (pin "19") (pinfunction "DBG_RXD_19") (pintype "passive"))
    )
    (net (code "113") (name "unconnected-(U2A-DBG_TXD-Pad20)") (class "Default")
      (node (ref "U2") (pin "20") (pinfunction "DBG_TXD_20") (pintype "passive"))
    )
    (net (code "114") (name "unconnected-(U2A-NETLIGHT-Pad18)") (class "Default")
      (node (ref "U2") (pin "18") (pinfunction "NETLIGHT_18") (pintype "passive"))
    )
    (net (code "115") (name "unconnected-(U2A-RESERVED-Pad1)") (class "Default")
      (node (ref "U2") (pin "1") (pinfunction "RESERVED_1") (pintype "passive"))
    )
    (net (code "116") (name "unconnected-(U2A-RESERVED-Pad3)") (class "Default")
      (node (ref "U2") (pin "3") (pinfunction "RESERVED_3") (pintype "passive"))
    )
    (net (code "117") (name "unconnected-(U2A-RESERVED-Pad4)") (class "Default")
      (node (ref "U2") (pin "4") (pinfunction "RESERVED_4") (pintype "passive"))
    )
    (net (code "118") (name "unconnected-(U2A-RESERVED-Pad5)") (class "Default")
      (node (ref "U2") (pin "5") (pinfunction "RESERVED_5") (pintype "passive"))
    )
    (net (code "119") (name "unconnected-(U2A-RESERVED-Pad6)") (class "Default")
      (node (ref "U2") (pin "6") (pinfunction "RESERVED_6") (pintype "passive"))
    )
    (net (code "120") (name "unconnected-(U2A-RESERVED-Pad7)") (class "Default")
      (node (ref "U2") (pin "7") (pinfunction "RESERVED_7") (pintype "passive"))
    )
    (net (code "121") (name "unconnected-(U2A-RESERVED-Pad8)") (class "Default")
      (node (ref "U2") (pin "8") (pinfunction "RESERVED_8") (pintype "passive"))
    )
    (net (code "122") (name "unconnected-(U2A-RESERVED-Pad9)") (class "Default")
      (node (ref "U2") (pin "9") (pinfunction "RESERVED_9") (pintype "passive"))
    )
    (net (code "123") (name "unconnected-(U2A-RESERVED-Pad10)") (class "Default")
      (node (ref "U2") (pin "10") (pinfunction "RESERVED_10") (pintype "passive"))
    )
    (net (code "124") (name "unconnected-(U2A-RESERVED-Pad11)") (class "Default")
      (node (ref "U2") (pin "11") (pinfunction "RESERVED_11") (pintype "passive"))
    )
    (net (code "125") (name "unconnected-(U2A-RESERVED-Pad12)") (class "Default")
      (node (ref "U2") (pin "12") (pinfunction "RESERVED_12") (pintype "passive"))
    )
    (net (code "126") (name "unconnected-(U2A-RESERVED-Pad13)") (class "Default")
      (node (ref "U2") (pin "13") (pinfunction "RESERVED_13") (pintype "passive"))
    )
    (net (code "127") (name "unconnected-(U2A-RESERVED-Pad14)") (class "Default")
      (node (ref "U2") (pin "14") (pinfunction "RESERVED_14") (pintype "passive"))
    )
    (net (code "128") (name "unconnected-(U2A-RESERVED-Pad16)") (class "Default")
      (node (ref "U2") (pin "16") (pinfunction "RESERVED_16") (pintype "passive"))
    )
    (net (code "129") (name "unconnected-(U2A-RESERVED-Pad17)") (class "Default")
      (node (ref "U2") (pin "17") (pinfunction "RESERVED_17") (pintype "passive"))
    )
    (net (code "130") (name "unconnected-(U2A-RESERVED-Pad22)") (class "Default")
      (node (ref "U2") (pin "22") (pinfunction "RESERVED_22") (pintype "passive"))
    )
    (net (code "131") (name "unconnected-(U2A-RESERVED-Pad23)") (class "Default")
      (node (ref "U2") (pin "23") (pinfunction "RESERVED_23") (pintype "passive"))
    )
    (net (code "132") (name "unconnected-(U2A-RESERVED-Pad24)") (class "Default")
      (node (ref "U2") (pin "24") (pinfunction "RESERVED_24") (pintype "passive"))
    )
    (net (code "133") (name "unconnected-(U2A-RESERVED-Pad25)") (class "Default")
      (node (ref "U2") (pin "25") (pinfunction "RESERVED_25") (pintype "passive"))
    )
    (net (code "134") (name "unconnected-(U2A-RESERVED-Pad27)") (class "Default")
      (node (ref "U2") (pin "27") (pinfunction "RESERVED_27") (pintype "passive"))
    )
    (net (code "135") (name "unconnected-(U2A-RESERVED-Pad28)") (class "Default")
      (node (ref "U2") (pin "28") (pinfunction "RESERVED_28") (pintype "passive"))
    )
    (net (code "136") (name "unconnected-(U2A-RESERVED-Pad31)") (class "Default")
      (node (ref "U2") (pin "31") (pinfunction "RESERVED_31") (pintype "passive"))
    )
    (net (code "137") (name "unconnected-(U2A-RESERVED-Pad32)") (class "Default")
      (node (ref "U2") (pin "32") (pinfunction "RESERVED_32") (pintype "passive"))
    )
    (net (code "138") (name "unconnected-(U2A-RESERVED-Pad33)") (class "Default")
      (node (ref "U2") (pin "33") (pinfunction "RESERVED_33") (pintype "passive"))
    )
    (net (code "139") (name "unconnected-(U2A-RESERVED-Pad35)") (class "Default")
      (node (ref "U2") (pin "35") (pinfunction "RESERVED_35") (pintype "passive"))
    )
    (net (code "140") (name "unconnected-(U2A-RESERVED-Pad36)") (class "Default")
      (node (ref "U2") (pin "36") (pinfunction "RESERVED_36") (pintype "passive"))
    )
    (net (code "141") (name "unconnected-(U2A-RESERVED-Pad37)") (class "Default")
      (node (ref "U2") (pin "37") (pinfunction "RESERVED_37") (pintype "passive"))
    )
    (net (code "142") (name "unconnected-(U2A-RESERVED-Pad44)") (class "Default")
      (node (ref "U2") (pin "44") (pinfunction "RESERVED_44") (pintype "passive"))
    )
    (net (code "143") (name "unconnected-(U2A-RESERVED-Pad49)") (class "Default")
      (node (ref "U2") (pin "49") (pinfunction "RESERVED_49") (pintype "passive"))
    )
    (net (code "144") (name "unconnected-(U2A-RESERVED-Pad50)") (class "Default")
      (node (ref "U2") (pin "50") (pinfunction "RESERVED_50") (pintype "passive"))
    )
    (net (code "145") (name "unconnected-(U2A-RI-Pad34)") (class "Default")
      (node (ref "U2") (pin "34") (pinfunction "RI_34") (pintype "passive"))
    )
    (net (code "146") (name "unconnected-(U2A-VDD_EXT-Pad26)") (class "Default")
      (node (ref "U2") (pin "26") (pinfunction "VDD_EXT_26") (pintype "passive"))
    )
    (net (code "147") (name "unconnected-(U3-VPP-Pad5)") (class "Default")
      (node (ref "U3") (pin "5") (pinfunction "VPP_5") (pintype "passive"))
    )
    (net (code "148") (name "unconnected-(U4-PA15{slash}JTDI-Pad38)") (class "Default")
      (node (ref "U4") (pin "38") (pinfunction "PA15/JTDI_38") (pintype "bidirectional"))
    )
    (net (code "149") (name "unconnected-(U4-PB0-Pad18)") (class "Default")
      (node (ref "U4") (pin "18") (pinfunction "PB0_18") (pintype "bidirectional"))
    )
    (net (code "150") (name "unconnected-(U4-PB1-Pad19)") (class "Default")
      (node (ref "U4") (pin "19") (pinfunction "PB1_19") (pintype "bidirectional"))
    )
    (net (code "151") (name "unconnected-(U4-PB15-Pad28)") (class "Default")
      (node (ref "U4") (pin "28") (pinfunction "PB15_28") (pintype "bidirectional"))
    )
    (net (code "152") (name "unconnected-(U4-PC13-TAMPER-RTC-Pad2)") (class "Default")
      (node (ref "U4") (pin "2") (pinfunction "PC13-TAMPER-RTC_2") (pintype "bidirectional"))
    )
    (net (code "153") (name "unconnected-(U5-CTS-Pad9)") (class "Default")
      (node (ref "U5") (pin "9") (pinfunction "CTS_9") (pintype "passive"))
    )
    (net (code "154") (name "unconnected-(U5-DSR-Pad10)") (class "Default")
      (node (ref "U5") (pin "10") (pinfunction "DSR_10") (pintype "passive"))
    )
    (net (code "155") (name "unconnected-(U5-DTR-Pad13)") (class "Default")
      (node (ref "U5") (pin "13") (pinfunction "DTR_13") (pintype "passive"))
    )
    (net (code "156") (name "unconnected-(U5-R233-Pad15)") (class "Default")
      (node (ref "U5") (pin "15") (pinfunction "R233_15") (pintype "passive"))
    )
    (net (code "157") (name "unconnected-(U5-RCD-Pad12)") (class "Default")
      (node (ref "U5") (pin "12") (pinfunction "RCD_12") (pintype "passive"))
    )
    (net (code "158") (name "unconnected-(U5-RI-Pad11)") (class "Default")
      (node (ref "U5") (pin "11") (pinfunction "RI_11") (pintype "passive"))
    )
    (net (code "159") (name "unconnected-(U5-RTS-Pad14)") (class "Default")
      (node (ref "U5") (pin "14") (pinfunction "RTS_14") (pintype "passive"))
    )
    (net (code "160") (name "unconnected-(U5-XD-Pad8)") (class "Default")
      (node (ref "U5") (pin "8") (pinfunction "XD_8") (pintype "passive"))
    )
    (net (code "161") (name "unconnected-(U5-XI-Pad7)") (class "Default")
      (node (ref "U5") (pin "7") (pinfunction "XI_7") (pintype "passive"))
    )
    (net (code "162") (name "unconnected-(U6-D2-Pad20)") (class "Default")
      (node (ref "U6") (pin "20") (pinfunction "D2_20") (pintype "passive+no_connect"))
    )
    (net (code "163") (name "unconnected-(U9-OUT-Pad2)") (class "Default")
      (node (ref "U9") (pin "2") (pinfunction "OUT_2") (pintype "passive"))
    )
    (net (code "164") (name "unconnected-(X1-Pad2)") (class "Default")
      (node (ref "X1") (pin "2") (pinfunction "2_2") (pintype "passive"))
    )
    (net (code "165") (name "unconnected-(X1-Pad4)") (class "Default")
      (node (ref "X1") (pin "4") (pinfunction "4_4") (pintype "passive"))
    )
  )
)
